# V1c.net
KiCad netlist of a schematic drawn in EAGLE
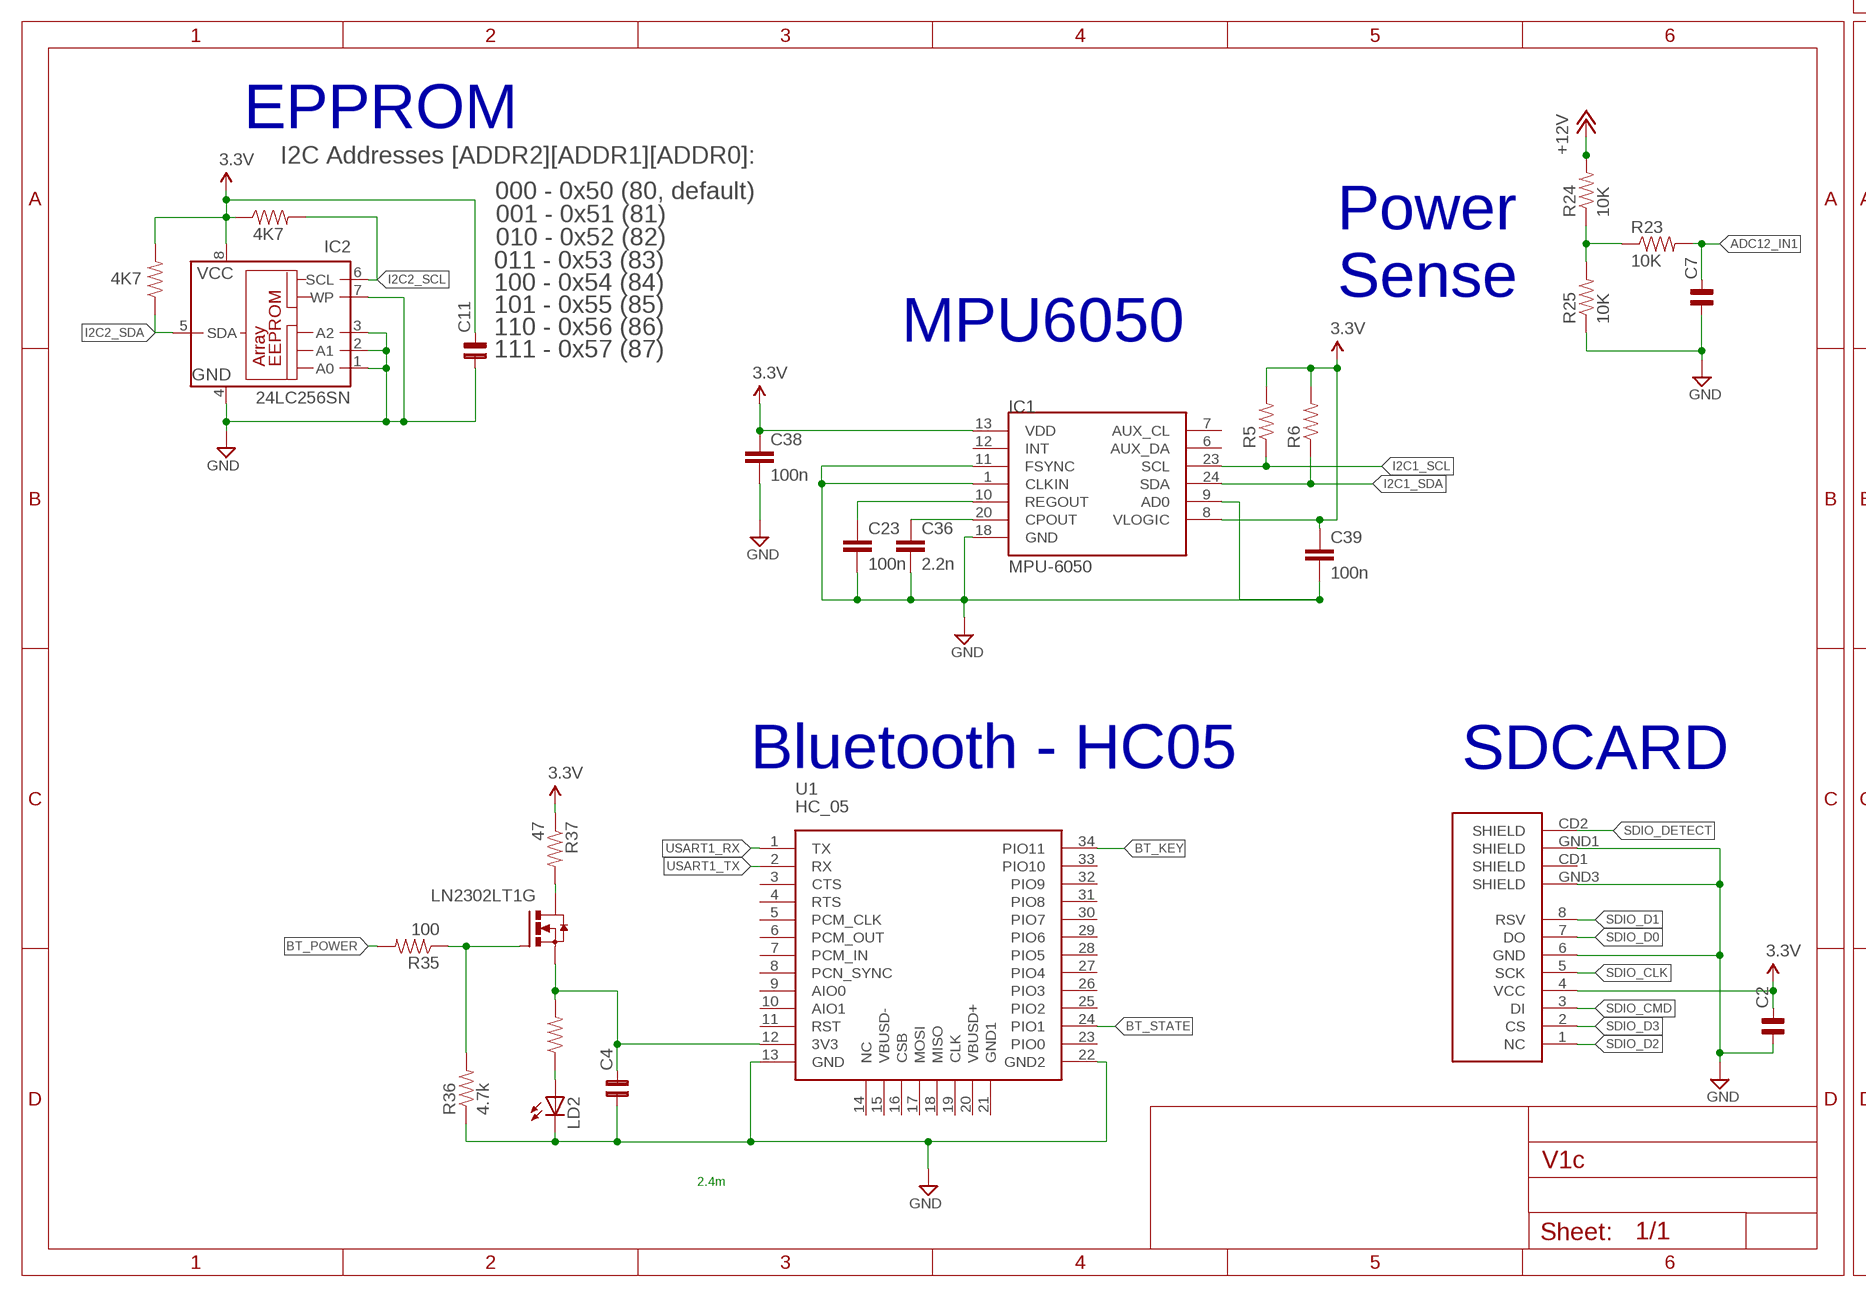
[diagram p0: schematic, sheet 1, part 1 of 2]
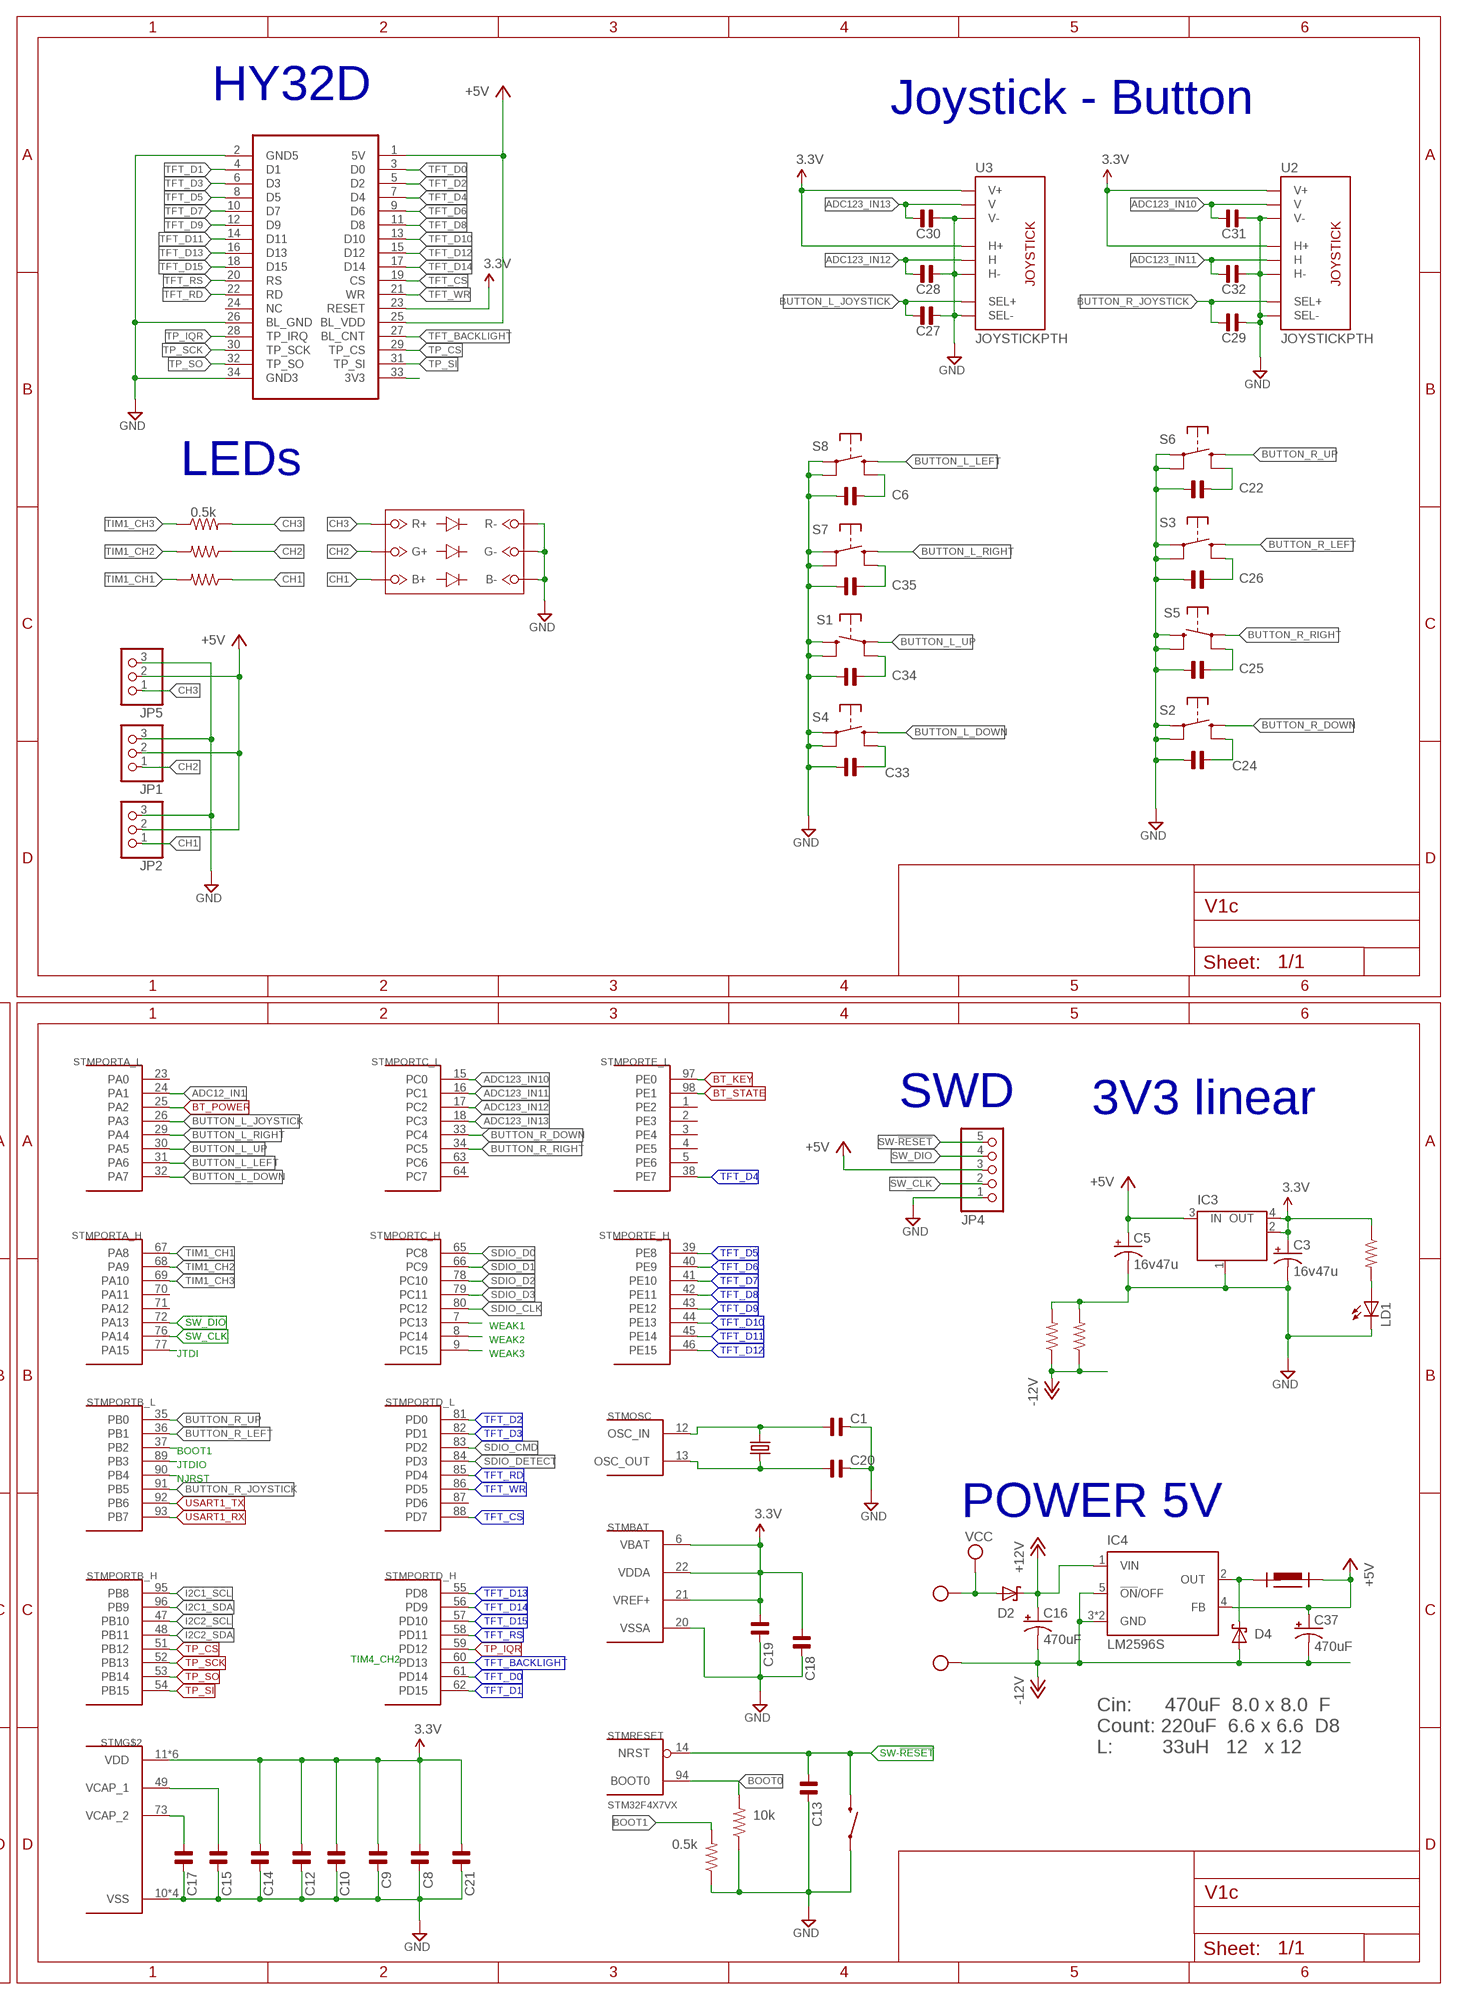
[diagram p1: schematic, sheet 1, part 2 of 2]

(export (version "E")
  (design (tool "Eeschema 10.0.6"))
  (components
    (comp (ref "C1")
      (value "C-NP-SMD-0603")
      (footprint "eagle-import:C-0603")
      (libsource (lib "eagle-import") (part "C-NP-SMD-0603"))
    )
    (comp (ref "C2")
      (value "C-NP-SMD-0603")
      (footprint "eagle-import:C-0603")
      (libsource (lib "eagle-import") (part "C-NP-SMD-0603"))
    )
    (comp (ref "C3")
      (value "16v47u")
      (footprint "eagle-import:SMC_C")
      (libsource (lib "eagle-import") (part "CPOL-USSMCC"))
    )
    (comp (ref "C4")
      (value "C-NP-SMD-0603")
      (footprint "eagle-import:C-0603")
      (libsource (lib "eagle-import") (part "C-NP-SMD-0603"))
    )
    (comp (ref "C5")
      (value "16v47u")
      (footprint "eagle-import:SMC_C")
      (libsource (lib "eagle-import") (part "CPOL-USSMCC"))
    )
    (comp (ref "C6")
      (value "C-NP-SMD-0603")
      (footprint "eagle-import:C-0603")
      (libsource (lib "eagle-import") (part "C-NP-SMD-0603"))
    )
    (comp (ref "C7")
      (value "C-NP-SMD-0603")
      (footprint "eagle-import:C-0603")
      (libsource (lib "eagle-import") (part "C-NP-SMD-0603"))
    )
    (comp (ref "C8")
      (value "C-NP-SMD-0603")
      (footprint "eagle-import:C-0603")
      (libsource (lib "eagle-import") (part "C-NP-SMD-0603"))
    )
    (comp (ref "C9")
      (value "C-NP-SMD-0603")
      (footprint "eagle-import:C-0603")
      (libsource (lib "eagle-import") (part "C-NP-SMD-0603"))
    )
    (comp (ref "C10")
      (value "C-NP-SMD-0603")
      (footprint "eagle-import:C-0603")
      (libsource (lib "eagle-import") (part "C-NP-SMD-0603"))
    )
    (comp (ref "C11")
      (value "C-NP-SMD-0603")
      (footprint "eagle-import:C-0603")
      (libsource (lib "eagle-import") (part "C-NP-SMD-0603"))
    )
    (comp (ref "C12")
      (value "C-NP-SMD-0603")
      (footprint "eagle-import:C-0603")
      (libsource (lib "eagle-import") (part "C-NP-SMD-0603"))
    )
    (comp (ref "C13")
      (value "C-NP-SMD-0603")
      (footprint "eagle-import:C-0603")
      (libsource (lib "eagle-import") (part "C-NP-SMD-0603"))
    )
    (comp (ref "C14")
      (value "C-NP-SMD-0603")
      (footprint "eagle-import:C-0603")
      (libsource (lib "eagle-import") (part "C-NP-SMD-0603"))
    )
    (comp (ref "C15")
      (value "C-NP-SMD-0603")
      (footprint "eagle-import:C-0603")
      (libsource (lib "eagle-import") (part "C-NP-SMD-0603"))
    )
    (comp (ref "C16")
      (value "470uF")
      (footprint "eagle-import:175TMP-0808")
      (libsource (lib "eagle-import") (part "CPOL-US175TMP-0808"))
    )
    (comp (ref "C17")
      (value "C-NP-SMD-0603")
      (footprint "eagle-import:C-0603")
      (libsource (lib "eagle-import") (part "C-NP-SMD-0603"))
    )
    (comp (ref "C18")
      (value "C-NP-SMD-0603")
      (footprint "eagle-import:C-0603")
      (libsource (lib "eagle-import") (part "C-NP-SMD-0603"))
    )
    (comp (ref "C19")
      (value "C-NP-SMD-0603")
      (footprint "eagle-import:C-0603")
      (libsource (lib "eagle-import") (part "C-NP-SMD-0603"))
    )
    (comp (ref "C20")
      (value "C-NP-SMD-0603")
      (footprint "eagle-import:C-0603")
      (libsource (lib "eagle-import") (part "C-NP-SMD-0603"))
    )
    (comp (ref "C21")
      (value "C-NP-SMD-0603")
      (footprint "eagle-import:C-0603")
      (libsource (lib "eagle-import") (part "C-NP-SMD-0603"))
    )
    (comp (ref "C22")
      (value "C-NP-SMD-0603")
      (footprint "eagle-import:C-0603")
      (libsource (lib "eagle-import") (part "C-NP-SMD-0603"))
    )
    (comp (ref "C23")
      (value "100n")
      (footprint "eagle-import:SPARKFUN_0603-CAP")
      (libsource (lib "eagle-import") (part "SPARKFUN_CAP0603-CAP"))
    )
    (comp (ref "C24")
      (value "C-NP-SMD-0603")
      (footprint "eagle-import:C-0603")
      (libsource (lib "eagle-import") (part "C-NP-SMD-0603"))
    )
    (comp (ref "C25")
      (value "C-NP-SMD-0603")
      (footprint "eagle-import:C-0603")
      (libsource (lib "eagle-import") (part "C-NP-SMD-0603"))
    )
    (comp (ref "C26")
      (value "C-NP-SMD-0603")
      (footprint "eagle-import:C-0603")
      (libsource (lib "eagle-import") (part "C-NP-SMD-0603"))
    )
    (comp (ref "C27")
      (value "C-NP-SMD-0603")
      (footprint "eagle-import:C-0603")
      (libsource (lib "eagle-import") (part "C-NP-SMD-0603"))
    )
    (comp (ref "C28")
      (value "C-NP-SMD-0603")
      (footprint "eagle-import:C-0603")
      (libsource (lib "eagle-import") (part "C-NP-SMD-0603"))
    )
    (comp (ref "C29")
      (value "C-NP-SMD-0603")
      (footprint "eagle-import:C-0603")
      (libsource (lib "eagle-import") (part "C-NP-SMD-0603"))
    )
    (comp (ref "C30")
      (value "C-NP-SMD-0603")
      (footprint "eagle-import:C-0603")
      (libsource (lib "eagle-import") (part "C-NP-SMD-0603"))
    )
    (comp (ref "C31")
      (value "C-NP-SMD-0603")
      (footprint "eagle-import:C-0603")
      (libsource (lib "eagle-import") (part "C-NP-SMD-0603"))
    )
    (comp (ref "C32")
      (value "C-NP-SMD-0603")
      (footprint "eagle-import:C-0603")
      (libsource (lib "eagle-import") (part "C-NP-SMD-0603"))
    )
    (comp (ref "C33")
      (value "C-NP-SMD-0603")
      (footprint "eagle-import:C-0603")
      (libsource (lib "eagle-import") (part "C-NP-SMD-0603"))
    )
    (comp (ref "C34")
      (value "C-NP-SMD-0603")
      (footprint "eagle-import:C-0603")
      (libsource (lib "eagle-import") (part "C-NP-SMD-0603"))
    )
    (comp (ref "C35")
      (value "C-NP-SMD-0603")
      (footprint "eagle-import:C-0603")
      (libsource (lib "eagle-import") (part "C-NP-SMD-0603"))
    )
    (comp (ref "C36")
      (value "2.2n")
      (footprint "eagle-import:SPARKFUN_0603-CAP")
      (libsource (lib "eagle-import") (part "SPARKFUN_CAP0603-CAP"))
    )
    (comp (ref "C37")
      (value "470uF")
      (footprint "eagle-import:E_7260-38W")
      (libsource (lib "eagle-import") (part "CPOL-USE/7260-38W"))
    )
    (comp (ref "C38")
      (value "100n")
      (footprint "eagle-import:SPARKFUN_0603-CAP")
      (libsource (lib "eagle-import") (part "SPARKFUN_CAP0603-CAP"))
    )
    (comp (ref "C39")
      (value "100n")
      (footprint "eagle-import:SPARKFUN_0603-CAP")
      (libsource (lib "eagle-import") (part "SPARKFUN_CAP0603-CAP"))
    )
    (comp (ref "D2")
      (value "MBRS330T3")
      (footprint "eagle-import:SMC")
      (libsource (lib "eagle-import") (part "MBRS30T33"))
    )
    (comp (ref "D4")
      (value "MBRS330T3")
      (footprint "eagle-import:SMC")
      (libsource (lib "eagle-import") (part "MBRS30T33"))
    )
    (comp (ref "IC1")
      (value "MPU-6050")
      (footprint "eagle-import:TESTING_QFN-24-4MM2")
      (libsource (lib "eagle-import") (part "TESTING_MPU-6050-1"))
    )
    (comp (ref "IC2")
      (value "24LC256SN")
      (footprint "eagle-import:SO-08")
      (fields (field (name "MF") "MICROCHIP") (field (name "MPN") "24LC256-I/SN"))
      (libsource (lib "eagle-import") (part "24SNLC256"))
    )
    (comp (ref "IC3")
      (value "LINEAR_MC33269ST-3.3T3")
      (footprint "eagle-import:LINEAR_SOT223")
      (libsource (lib "eagle-import") (part "LINEAR_MC33269ST-3.3T3"))
    )
    (comp (ref "IC4")
      (value "LM2596S")
      (footprint "eagle-import:TO263-5")
      (fields (field (name "MF") "NATIONAL SEMICONDUCTOR") (field (name "MPN") "LM2596S-ADJ/NOPB"))
      (libsource (lib "eagle-import") (part "LM2596S"))
    )
    (comp (ref "JP1")
      (value "PINHD-1X3_2.54-90°")
      (footprint "eagle-import:1X03_90")
      (libsource (lib "eagle-import") (part "PINHD-1X3_2.54-90°"))
    )
    (comp (ref "JP2")
      (value "PINHD-1X3_2.54-90°")
      (footprint "eagle-import:1X03_90")
      (libsource (lib "eagle-import") (part "PINHD-1X3_2.54-90°"))
    )
    (comp (ref "JP4")
      (value "PINHD-1X5_2.54-90°")
      (footprint "eagle-import:1X05_90")
      (libsource (lib "eagle-import") (part "PINHD-1X5_2.54-90°"))
    )
    (comp (ref "JP5")
      (value "PINHD-1X3_2.54-90°")
      (footprint "eagle-import:1X03_90")
      (libsource (lib "eagle-import") (part "PINHD-1X3_2.54-90°"))
    )
    (comp (ref "LD1")
      (value "LEDCHIPLED_0805")
      (footprint "eagle-import:CHIPLED_0805")
      (libsource (lib "eagle-import") (part "LEDCHIPLED_0805"))
    )
    (comp (ref "LD2")
      (value "LEDCHIPLED_0805")
      (footprint "eagle-import:CHIPLED_0805")
      (libsource (lib "eagle-import") (part "LEDCHIPLED_0805"))
    )
    (comp (ref "LN2302LT1G")
      (value "FDN327N")
      (footprint "eagle-import:SOT-23")
      (libsource (lib "eagle-import") (part "FDN327N"))
    )
    (comp (ref "R1")
      (value "10k")
      (footprint "eagle-import:SPARKFUN_0603-RES")
      (libsource (lib "eagle-import") (part "Robotech_RCL_SPARKFUN_RESISTOR0603-RES"))
    )
    (comp (ref "R2")
      (value "10k")
      (footprint "eagle-import:SPARKFUN_0603-RES")
      (libsource (lib "eagle-import") (part "Robotech_RCL_SPARKFUN_RESISTOR0603-RES"))
    )
    (comp (ref "R5")
      (value "SPARKFUN_RESISTOR0603-RES")
      (footprint "eagle-import:SPARKFUN_0603-RES")
      (libsource (lib "eagle-import") (part "Helios_RLC_SPARKFUN_RESISTOR0603-RES"))
    )
    (comp (ref "R6")
      (value "SPARKFUN_RESISTOR0603-RES")
      (footprint "eagle-import:SPARKFUN_0603-RES")
      (libsource (lib "eagle-import") (part "Helios_RLC_SPARKFUN_RESISTOR0603-RES"))
    )
    (comp (ref "R7")
      (value "10k")
      (footprint "eagle-import:SPARKFUN_0603-RES")
      (libsource (lib "eagle-import") (part "Robotech_RCL_SPARKFUN_RESISTOR0603-RES"))
    )
    (comp (ref "R8")
      (value "0.5k")
      (footprint "eagle-import:SPARKFUN_0603-RES")
      (libsource (lib "eagle-import") (part "Robotech_RCL_SPARKFUN_RESISTOR0603-RES"))
    )
    (comp (ref "R9")
      (value "10K")
      (footprint "eagle-import:SPARKFUN_0603-RES")
      (libsource (lib "eagle-import") (part "Robotech_RCL_SPARKFUN_RESISTOR0603-RES"))
    )
    (comp (ref "R10")
      (value "10K")
      (footprint "eagle-import:SPARKFUN_0603-RES")
      (libsource (lib "eagle-import") (part "Robotech_RCL_SPARKFUN_RESISTOR0603-RES"))
    )
    (comp (ref "R11")
      (value "10K")
      (footprint "eagle-import:SPARKFUN_0603-RES")
      (libsource (lib "eagle-import") (part "Robotech_RCL_SPARKFUN_RESISTOR0603-RES"))
    )
    (comp (ref "R12")
      (value "10K")
      (footprint "eagle-import:SPARKFUN_0603-RES")
      (fields (field (name "R32") "0.5k"))
      (libsource (lib "eagle-import") (part "Robotech_RCL_SPARKFUN_RESISTOR0603-RES"))
    )
    (comp (ref "R15")
      (value "4K7")
      (footprint "eagle-import:SPARKFUN_0603-RES")
      (libsource (lib "eagle-import") (part "Robotech_RCL_SPARKFUN_RESISTOR0603-RES"))
    )
    (comp (ref "R16")
      (value "4K7")
      (footprint "eagle-import:SPARKFUN_0603-RES")
      (libsource (lib "eagle-import") (part "Robotech_RCL_SPARKFUN_RESISTOR0603-RES"))
    )
    (comp (ref "R23")
      (value "10K")
      (footprint "eagle-import:SPARKFUN_0603-RES")
      (libsource (lib "eagle-import") (part "Robotech_RCL_SPARKFUN_RESISTOR0603-RES"))
    )
    (comp (ref "R24")
      (value "10K")
      (footprint "eagle-import:SPARKFUN_0603-RES")
      (libsource (lib "eagle-import") (part "Robotech_RCL_SPARKFUN_RESISTOR0603-RES"))
    )
    (comp (ref "R25")
      (value "10K")
      (footprint "eagle-import:SPARKFUN_0603-RES")
      (libsource (lib "eagle-import") (part "Robotech_RCL_SPARKFUN_RESISTOR0603-RES"))
    )
    (comp (ref "R35")
      (value "100")
      (footprint "eagle-import:SPARKFUN_0603-RES")
      (libsource (lib "eagle-import") (part "SPARKFUN_RESISTOR0603-RES"))
    )
    (comp (ref "R36")
      (value "4.7k")
      (footprint "eagle-import:SPARKFUN_0603-RES")
      (libsource (lib "eagle-import") (part "SPARKFUN_RESISTOR0603-RES"))
    )
    (comp (ref "R37")
      (value "47")
      (footprint "eagle-import:SPARKFUN_0603-RES")
      (libsource (lib "eagle-import") (part "SPARKFUN_RESISTOR0603-RES"))
    )
    (comp (ref "R39")
      (value "10K")
      (footprint "eagle-import:SPARKFUN_0603-RES")
      (libsource (lib "eagle-import") (part "Robotech_RCL_SPARKFUN_RESISTOR0603-RES"))
    )
    (comp (ref "S1")
      (value "RACON12/")
      (footprint "eagle-import:RACON12_")
      (libsource (lib "eagle-import") (part "RACON12/"))
    )
    (comp (ref "S2")
      (value "RACON12/")
      (footprint "eagle-import:RACON12_")
      (libsource (lib "eagle-import") (part "RACON12/"))
    )
    (comp (ref "S3")
      (value "RACON12/")
      (footprint "eagle-import:RACON12_")
      (libsource (lib "eagle-import") (part "RACON12/"))
    )
    (comp (ref "S4")
      (value "RACON12/")
      (footprint "eagle-import:RACON12_")
      (libsource (lib "eagle-import") (part "RACON12/"))
    )
    (comp (ref "S5")
      (value "RACON12/")
      (footprint "eagle-import:RACON12_")
      (libsource (lib "eagle-import") (part "RACON12/"))
    )
    (comp (ref "S6")
      (value "RACON12/")
      (footprint "eagle-import:RACON12_")
      (libsource (lib "eagle-import") (part "RACON12/"))
    )
    (comp (ref "S7")
      (value "RACON12/")
      (footprint "eagle-import:RACON12_")
      (libsource (lib "eagle-import") (part "RACON12/"))
    )
    (comp (ref "S8")
      (value "RACON12/")
      (footprint "eagle-import:RACON12_")
      (libsource (lib "eagle-import") (part "RACON12/"))
    )
    (comp (ref "S9")
      (value "RESET")
      (footprint "eagle-import:TACTILE-SWITCH-1101NE")
      (fields (field (name "PARTNO") "EVQ-P7J01P"))
      (libsource (lib "eagle-import") (part "SWITCH-MOMENTARY-2-SMD-1101NE"))
    )
    (comp (ref "SDCARD2")
      (value "microSD Socket")
      (footprint "eagle-import:MICRO-SD-SOCKET-PP")
      (libsource (lib "eagle-import") (part "USD-SOCKETNEW"))
    )
    (comp (ref "STM")
      (value "STM32F4X7VX")
      (footprint "eagle-import:TQFP100")
      (fields (field (name "PARTNO") "STM32F427VI"))
      (libsource (lib "eagle-import") (part "STM32F4X7VX"))
    )
    (comp (ref "U$3")
      (value "TFT3.2")
      (footprint "eagle-import:HY32D_2")
      (libsource (lib "eagle-import") (part "TFT3.2"))
    )
    (comp (ref "U$5")
      (value "BIG_INDUCTOR")
      (footprint "eagle-import:12X12")
      (libsource (lib "eagle-import") (part "BIG_INDUCTOR"))
    )
    (comp (ref "U$13")
      (value "RGB_LED")
      (footprint "eagle-import:SMD")
      (libsource (lib "eagle-import") (part "RGB_LED"))
    )
    (comp (ref "U1")
      (value "HC_05")
      (footprint "eagle-import:BLUETOOTH_SMD")
      (libsource (lib "eagle-import") (part "HC_05"))
    )
    (comp (ref "U2")
      (value "JOYSTICKPTH")
      (footprint "eagle-import:JOYSTICK")
      (libsource (lib "eagle-import") (part "JOYSTICKPTH"))
    )
    (comp (ref "U3")
      (value "JOYSTICKPTH")
      (footprint "eagle-import:JOYSTICK")
      (libsource (lib "eagle-import") (part "JOYSTICKPTH"))
    )
    (comp (ref "X1")
      (value "MKDSN1,5/2-5,08")
      (footprint "eagle-import:MKDSN1,5_2-5,08")
      (fields (field (name "MPN") "MKDSN 1,5/2-5.08"))
      (libsource (lib "eagle-import") (part "MKDSN1,5/2-5,08"))
    )
    (comp (ref "Y1")
      (value "CRYSTALHC49US")
      (footprint "eagle-import:HC49US")
      (libsource (lib "eagle-import") (part "CRYSTALHC49US"))
    )
  )
  (nets
    (net (code "1") (name "+5V") (class "Default")
      (node (ref "C37") (pin "+") (pinfunction "+_+") (pintype "passive"))
      (node (ref "C5") (pin "+") (pinfunction "+_+") (pintype "passive"))
      (node (ref "IC3") (pin "3") (pinfunction "IN_3") (pintype "input"))
      (node (ref "IC4") (pin "4") (pinfunction "FB_4") (pintype "input"))
      (node (ref "JP1") (pin "2") (pinfunction "2_2") (pintype "passive"))
      (node (ref "JP2") (pin "2") (pinfunction "2_2") (pintype "passive"))
      (node (ref "JP4") (pin "3") (pinfunction "3_3") (pintype "passive"))
      (node (ref "JP5") (pin "2") (pinfunction "2_2") (pintype "passive"))
      (node (ref "U$3") (pin "1") (pinfunction "5V_1") (pintype "bidirectional"))
      (node (ref "U$3") (pin "25") (pinfunction "BL_VDD_25") (pintype "bidirectional"))
      (node (ref "U$5") (pin "P$1") (pinfunction "P$1_P$1") (pintype "bidirectional"))
    )
    (net (code "2") (name "+12V") (class "Default")
      (node (ref "C16") (pin "+") (pinfunction "+_+") (pintype "passive"))
      (node (ref "D2") (pin "C") (pinfunction "C_C") (pintype "passive"))
      (node (ref "IC4") (pin "1") (pinfunction "VIN_1") (pintype "input"))
      (node (ref "R24") (pin "2") (pinfunction "2_2") (pintype "passive"))
    )
    (net (code "3") (name "-12V") (class "Default")
      (node (ref "C16") (pin "-") (pinfunction "-_-") (pintype "passive"))
      (node (ref "C37") (pin "-") (pinfunction "-_-") (pintype "passive"))
      (node (ref "D4") (pin "A") (pinfunction "A_A") (pintype "passive"))
      (node (ref "IC4") (pin "3") (pinfunction "GND_3") (pintype "power_in"))
      (node (ref "IC4") (pin "5") (pinfunction "~{ON}/OFF_5") (pintype "input"))
      (node (ref "IC4") (pin "6") (pinfunction "GND_6") (pintype "power_in"))
      (node (ref "R1") (pin "1") (pinfunction "1_1") (pintype "passive"))
      (node (ref "R2") (pin "1") (pinfunction "1_1") (pintype "passive"))
      (node (ref "X1") (pin "1") (pinfunction "KL_1") (pintype "passive"))
    )
    (net (code "4") (name "/JTDI") (class "Default")
      (node (ref "STM") (pin "77") (pinfunction "PA15_77") (pintype "bidirectional"))
    )
    (net (code "5") (name "/JTDIO") (class "Default")
      (node (ref "STM") (pin "89") (pinfunction "PB3_89") (pintype "bidirectional"))
    )
    (net (code "6") (name "/NJRST") (class "Default")
      (node (ref "STM") (pin "90") (pinfunction "PB4_90") (pintype "bidirectional"))
    )
    (net (code "7") (name "/SW-~{RESET}") (class "Default")
      (node (ref "C13") (pin "1") (pinfunction "1_1") (pintype "passive"))
      (node (ref "JP4") (pin "5") (pinfunction "5_5") (pintype "passive"))
      (node (ref "S9") (pin "P$2") (pinfunction "2_P$2") (pintype "passive"))
      (node (ref "STM") (pin "14") (pinfunction "NRST_14") (pintype "input"))
    )
    (net (code "8") (name "/WEAK1") (class "Default")
      (node (ref "STM") (pin "7") (pinfunction "PC13_7") (pintype "bidirectional"))
    )
    (net (code "9") (name "/WEAK2") (class "Default")
      (node (ref "STM") (pin "8") (pinfunction "PC14_8") (pintype "bidirectional"))
    )
    (net (code "10") (name "/WEAK3") (class "Default")
      (node (ref "STM") (pin "9") (pinfunction "PC15_9") (pintype "bidirectional"))
    )
    (net (code "11") (name "3.3V") (class "Default")
      (node (ref "C10") (pin "1") (pinfunction "1_1") (pintype "passive"))
      (node (ref "C11") (pin "2") (pinfunction "2_2") (pintype "passive"))
      (node (ref "C12") (pin "1") (pinfunction "1_1") (pintype "passive"))
      (node (ref "C14") (pin "1") (pinfunction "1_1") (pintype "passive"))
      (node (ref "C18") (pin "1") (pinfunction "1_1") (pintype "passive"))
      (node (ref "C19") (pin "1") (pinfunction "1_1") (pintype "passive"))
      (node (ref "C2") (pin "2") (pinfunction "2_2") (pintype "passive"))
      (node (ref "C21") (pin "1") (pinfunction "1_1") (pintype "passive"))
      (node (ref "C3") (pin "+") (pinfunction "+_+") (pintype "passive"))
      (node (ref "C38") (pin "1") (pinfunction "1_1") (pintype "passive"))
      (node (ref "C39") (pin "1") (pinfunction "1_1") (pintype "passive"))
      (node (ref "C8") (pin "1") (pinfunction "1_1") (pintype "passive"))
      (node (ref "C9") (pin "1") (pinfunction "1_1") (pintype "passive"))
      (node (ref "IC1") (pin "13") (pinfunction "VDD_13") (pintype "bidirectional"))
      (node (ref "IC1") (pin "8") (pinfunction "VLOGIC_8") (pintype "bidirectional"))
      (node (ref "IC2") (pin "8") (pinfunction "VCC_8") (pintype "power_in"))
      (node (ref "IC3") (pin "2") (pinfunction "OUT_2") (pintype "passive"))
      (node (ref "IC3") (pin "4") (pinfunction "OUT_4") (pintype "passive"))
      (node (ref "R15") (pin "1") (pinfunction "1_1") (pintype "passive"))
      (node (ref "R16") (pin "2") (pinfunction "2_2") (pintype "passive"))
      (node (ref "R37") (pin "1") (pinfunction "1_1") (pintype "passive"))
      (node (ref "R5") (pin "2") (pinfunction "2_2") (pintype "passive"))
      (node (ref "R6") (pin "2") (pinfunction "2_2") (pintype "passive"))
      (node (ref "R9") (pin "1") (pinfunction "1_1") (pintype "passive"))
      (node (ref "SDCARD2") (pin "4") (pinfunction "VCC_4") (pintype "bidirectional"))
      (node (ref "STM") (pin "100") (pinfunction "VDD_100") (pintype "power_in"))
      (node (ref "STM") (pin "11") (pinfunction "VDD_11") (pintype "power_in"))
      (node (ref "STM") (pin "19") (pinfunction "VDD_19") (pintype "power_in"))
      (node (ref "STM") (pin "21") (pinfunction "VREF+_21") (pintype "input"))
      (node (ref "STM") (pin "22") (pinfunction "VDDA_22") (pintype "power_in"))
      (node (ref "STM") (pin "28") (pinfunction "VDD_28") (pintype "power_in"))
      (node (ref "STM") (pin "50") (pinfunction "VDD_50") (pintype "power_in"))
      (node (ref "STM") (pin "6") (pinfunction "VBAT_6") (pintype "power_in"))
      (node (ref "STM") (pin "75") (pinfunction "VDD_75") (pintype "power_in"))
      (node (ref "U$3") (pin "23") (pinfunction "RESET_23") (pintype "bidirectional"))
      (node (ref "U2") (pin "H1") (pinfunction "H+_H1") (pintype "bidirectional"))
      (node (ref "U2") (pin "V1") (pinfunction "V+_V1") (pintype "bidirectional"))
      (node (ref "U3") (pin "H1") (pinfunction "H+_H1") (pintype "bidirectional"))
      (node (ref "U3") (pin "V1") (pinfunction "V+_V1") (pintype "bidirectional"))
    )
    (net (code "12") (name "ADC12_IN1") (class "Default")
      (node (ref "C7") (pin "2") (pinfunction "2_2") (pintype "passive"))
      (node (ref "R23") (pin "2") (pinfunction "2_2") (pintype "passive"))
      (node (ref "STM") (pin "24") (pinfunction "PA1_24") (pintype "bidirectional"))
    )
    (net (code "13") (name "ADC123_IN10") (class "Default")
      (node (ref "C31") (pin "1") (pinfunction "1_1") (pintype "passive"))
      (node (ref "STM") (pin "15") (pinfunction "PC0_15") (pintype "bidirectional"))
      (node (ref "U2") (pin "V2") (pinfunction "V_V2") (pintype "bidirectional"))
    )
    (net (code "14") (name "ADC123_IN11") (class "Default")
      (node (ref "C32") (pin "1") (pinfunction "1_1") (pintype "passive"))
      (node (ref "STM") (pin "16") (pinfunction "PC1_16") (pintype "bidirectional"))
      (node (ref "U2") (pin "H2") (pinfunction "H_H2") (pintype "bidirectional"))
    )
    (net (code "15") (name "ADC123_IN12") (class "Default")
      (node (ref "C28") (pin "1") (pinfunction "1_1") (pintype "passive"))
      (node (ref "STM") (pin "17") (pinfunction "PC2_17") (pintype "bidirectional"))
      (node (ref "U3") (pin "H2") (pinfunction "H_H2") (pintype "bidirectional"))
    )
    (net (code "16") (name "ADC123_IN13") (class "Default")
      (node (ref "C30") (pin "1") (pinfunction "1_1") (pintype "passive"))
      (node (ref "STM") (pin "18") (pinfunction "PC3_18") (pintype "bidirectional"))
      (node (ref "U3") (pin "V2") (pinfunction "V_V2") (pintype "bidirectional"))
    )
    (net (code "17") (name "BOOT0") (class "Default")
      (node (ref "R7") (pin "2") (pinfunction "2_2") (pintype "passive"))
      (node (ref "STM") (pin "94") (pinfunction "BOOT0_94") (pintype "input"))
    )
    (net (code "18") (name "BOOT1") (class "Default")
      (node (ref "R8") (pin "2") (pinfunction "2_2") (pintype "passive"))
      (node (ref "STM") (pin "37") (pinfunction "PB2_37") (pintype "bidirectional"))
    )
    (net (code "19") (name "BT_KEY") (class "Default")
      (node (ref "STM") (pin "97") (pinfunction "PE0_97") (pintype "bidirectional"))
      (node (ref "U1") (pin "34") (pinfunction "PIO11_34") (pintype "bidirectional"))
    )
    (net (code "20") (name "BT_POWER") (class "Default")
      (node (ref "R35") (pin "2") (pinfunction "2_2") (pintype "passive"))
      (node (ref "STM") (pin "25") (pinfunction "PA2_25") (pintype "bidirectional"))
    )
    (net (code "21") (name "BT_STATE") (class "Default")
      (node (ref "STM") (pin "98") (pinfunction "PE1_98") (pintype "bidirectional"))
      (node (ref "U1") (pin "24") (pinfunction "PIO1_24") (pintype "bidirectional"))
    )
    (net (code "22") (name "BUTTON_L_DOWN") (class "Default")
      (node (ref "S4") (pin "1") (pinfunction "S_1") (pintype "passive"))
      (node (ref "STM") (pin "32") (pinfunction "PA7_32") (pintype "bidirectional"))
    )
    (net (code "23") (name "BUTTON_L_JOYSTICK") (class "Default")
      (node (ref "C27") (pin "1") (pinfunction "1_1") (pintype "passive"))
      (node (ref "STM") (pin "26") (pinfunction "PA3_26") (pintype "bidirectional"))
      (node (ref "U3") (pin "B1A") (pinfunction "SEL+_B1A") (pintype "bidirectional"))
    )
    (net (code "24") (name "BUTTON_L_LEFT") (class "Default")
      (node (ref "S8") (pin "1") (pinfunction "S_1") (pintype "passive"))
      (node (ref "STM") (pin "31") (pinfunction "PA6_31") (pintype "bidirectional"))
    )
    (net (code "25") (name "BUTTON_L_RIGHT") (class "Default")
      (node (ref "S7") (pin "1") (pinfunction "S_1") (pintype "passive"))
      (node (ref "STM") (pin "29") (pinfunction "PA4_29") (pintype "bidirectional"))
    )
    (net (code "26") (name "BUTTON_L_UP") (class "Default")
      (node (ref "S1") (pin "3") (pinfunction "P_3") (pintype "passive"))
      (node (ref "STM") (pin "30") (pinfunction "PA5_30") (pintype "bidirectional"))
    )
    (net (code "27") (name "BUTTON_R_DOWN") (class "Default")
      (node (ref "S2") (pin "1") (pinfunction "S_1") (pintype "passive"))
      (node (ref "STM") (pin "33") (pinfunction "PC4_33") (pintype "bidirectional"))
    )
    (net (code "28") (name "BUTTON_R_JOYSTICK") (class "Default")
      (node (ref "C29") (pin "1") (pinfunction "1_1") (pintype "passive"))
      (node (ref "STM") (pin "91") (pinfunction "PB5_91") (pintype "bidirectional"))
      (node (ref "U2") (pin "B1A") (pinfunction "SEL+_B1A") (pintype "bidirectional"))
    )
    (net (code "29") (name "BUTTON_R_LEFT") (class "Default")
      (node (ref "S3") (pin "1") (pinfunction "S_1") (pintype "passive"))
      (node (ref "STM") (pin "36") (pinfunction "PB1_36") (pintype "bidirectional"))
    )
    (net (code "30") (name "BUTTON_R_RIGHT") (class "Default")
      (node (ref "S5") (pin "3") (pinfunction "P_3") (pintype "passive"))
      (node (ref "STM") (pin "34") (pinfunction "PC5_34") (pintype "bidirectional"))
    )
    (net (code "31") (name "BUTTON_R_UP") (class "Default")
      (node (ref "S6") (pin "1") (pinfunction "S_1") (pintype "passive"))
      (node (ref "STM") (pin "35") (pinfunction "PB0_35") (pintype "bidirectional"))
    )
    (net (code "32") (name "CH1") (class "Default")
      (node (ref "JP2") (pin "1") (pinfunction "1_1") (pintype "passive"))
      (node (ref "R11") (pin "1") (pinfunction "1_1") (pintype "passive"))
      (node (ref "U$13") (pin "B+") (pinfunction "B+_B+") (pintype "bidirectional"))
    )
    (net (code "33") (name "CH2") (class "Default")
      (node (ref "JP1") (pin "1") (pinfunction "1_1") (pintype "passive"))
      (node (ref "R39") (pin "1") (pinfunction "1_1") (pintype "passive"))
      (node (ref "U$13") (pin "G+") (pinfunction "G+_G+") (pintype "bidirectional"))
    )
    (net (code "34") (name "CH3") (class "Default")
      (node (ref "JP5") (pin "1") (pinfunction "1_1") (pintype "passive"))
      (node (ref "R12") (pin "2") (pinfunction "2_2") (pintype "passive"))
      (node (ref "U$13") (pin "R+") (pinfunction "R+_R+") (pintype "bidirectional"))
    )
    (net (code "35") (name "GND") (class "Default")
      (node (ref "C1") (pin "2") (pinfunction "2_2") (pintype "passive"))
      (node (ref "C10") (pin "2") (pinfunction "2_2") (pintype "passive"))
      (node (ref "C11") (pin "1") (pinfunction "1_1") (pintype "passive"))
      (node (ref "C12") (pin "2") (pinfunction "2_2") (pintype "passive"))
      (node (ref "C13") (pin "2") (pinfunction "2_2") (pintype "passive"))
      (node (ref "C14") (pin "2") (pinfunction "2_2") (pintype "passive"))
      (node (ref "C15") (pin "2") (pinfunction "2_2") (pintype "passive"))
      (node (ref "C17") (pin "2") (pinfunction "2_2") (pintype "passive"))
      (node (ref "C18") (pin "2") (pinfunction "2_2") (pintype "passive"))
      (node (ref "C19") (pin "2") (pinfunction "2_2") (pintype "passive"))
      (node (ref "C2") (pin "1") (pinfunction "1_1") (pintype "passive"))
      (node (ref "C20") (pin "2") (pinfunction "2_2") (pintype "passive"))
      (node (ref "C21") (pin "2") (pinfunction "2_2") (pintype "passive"))
      (node (ref "C22") (pin "1") (pinfunction "1_1") (pintype "passive"))
      (node (ref "C23") (pin "2") (pinfunction "2_2") (pintype "passive"))
      (node (ref "C24") (pin "2") (pinfunction "2_2") (pintype "passive"))
      (node (ref "C25") (pin "2") (pinfunction "2_2") (pintype "passive"))
      (node (ref "C26") (pin "2") (pinfunction "2_2") (pintype "passive"))
      (node (ref "C27") (pin "2") (pinfunction "2_2") (pintype "passive"))
      (node (ref "C28") (pin "2") (pinfunction "2_2") (pintype "passive"))
      (node (ref "C29") (pin "2") (pinfunction "2_2") (pintype "passive"))
      (node (ref "C3") (pin "-") (pinfunction "-_-") (pintype "passive"))
      (node (ref "C30") (pin "2") (pinfunction "2_2") (pintype "passive"))
      (node (ref "C31") (pin "2") (pinfunction "2_2") (pintype "passive"))
      (node (ref "C32") (pin "2") (pinfunction "2_2") (pintype "passive"))
      (node (ref "C33") (pin "2") (pinfunction "2_2") (pintype "passive"))
      (node (ref "C34") (pin "2") (pinfunction "2_2") (pintype "passive"))
      (node (ref "C35") (pin "2") (pinfunction "2_2") (pintype "passive"))
      (node (ref "C36") (pin "2") (pinfunction "2_2") (pintype "passive"))
      (node (ref "C38") (pin "2") (pinfunction "2_2") (pintype "passive"))
      (node (ref "C39") (pin "2") (pinfunction "2_2") (pintype "passive"))
      (node (ref "C4") (pin "1") (pinfunction "1_1") (pintype "passive"))
      (node (ref "C5") (pin "-") (pinfunction "-_-") (pintype "passive"))
      (node (ref "C6") (pin "1") (pinfunction "1_1") (pintype "passive"))
      (node (ref "C7") (pin "1") (pinfunction "1_1") (pintype "passive"))
      (node (ref "C8") (pin "2") (pinfunction "2_2") (pintype "passive"))
      (node (ref "C9") (pin "2") (pinfunction "2_2") (pintype "passive"))
      (node (ref "IC1") (pin "1") (pinfunction "CLKIN_1") (pintype "bidirectional"))
      (node (ref "IC1") (pin "11") (pinfunction "FSYNC_11") (pintype "bidirectional"))
      (node (ref "IC1") (pin "18") (pinfunction "GND_18") (pintype "bidirectional"))
      (node (ref "IC1") (pin "9") (pinfunction "AD0_9") (pintype "bidirectional"))
      (node (ref "IC2") (pin "1") (pinfunction "A0_1") (pintype "input"))
      (node (ref "IC2") (pin "2") (pinfunction "A1_2") (pintype "input"))
      (node (ref "IC2") (pin "3") (pinfunction "A2_3") (pintype "input"))
      (node (ref "IC2") (pin "4") (pinfunction "GND_4") (pintype "power_in"))
      (node (ref "IC2") (pin "7") (pinfunction "WP_7") (pintype "input"))
      (node (ref "IC3") (pin "1") (pinfunction "GND/ADJ_1") (pintype "input"))
      (node (ref "JP1") (pin "3") (pinfunction "3_3") (pintype "passive"))
      (node (ref "JP2") (pin "3") (pinfunction "3_3") (pintype "passive"))
      (node (ref "JP4") (pin "1") (pinfunction "1_1") (pintype "passive"))
      (node (ref "JP5") (pin "3") (pinfunction "3_3") (pintype "passive"))
      (node (ref "LD1") (pin "C") (pinfunction "C_C") (pintype "passive"))
      (node (ref "LD2") (pin "C") (pinfunction "C_C") (pintype "passive"))
      (node (ref "R1") (pin "2") (pinfunction "2_2") (pintype "passive"))
      (node (ref "R2") (pin "2") (pinfunction "2_2") (pintype "passive"))
      (node (ref "R25") (pin "1") (pinfunction "1_1") (pintype "passive"))
      (node (ref "R36") (pin "1") (pinfunction "1_1") (pintype "passive"))
      (node (ref "R7") (pin "1") (pinfunction "1_1") (pintype "passive"))
      (node (ref "R8") (pin "1") (pinfunction "1_1") (pintype "passive"))
      (node (ref "S1") (pin "1") (pinfunction "S_1") (pintype "passive"))
      (node (ref "S1") (pin "2") (pinfunction "S_2") (pintype "passive"))
      (node (ref "S2") (pin "3") (pinfunction "P_3") (pintype "passive"))
      (node (ref "S2") (pin "4") (pinfunction "P_4") (pintype "passive"))
      (node (ref "S3") (pin "3") (pinfunction "P_3") (pintype "passive"))
      (node (ref "S3") (pin "4") (pinfunction "P_4") (pintype "passive"))
      (node (ref "S4") (pin "3") (pinfunction "P_3") (pintype "passive"))
      (node (ref "S4") (pin "4") (pinfunction "P_4") (pintype "passive"))
      (node (ref "S5") (pin "1") (pinfunction "S_1") (pintype "passive"))
      (node (ref "S5") (pin "2") (pinfunction "S_2") (pintype "passive"))
      (node (ref "S6") (pin "3") (pinfunction "P_3") (pintype "passive"))
      (node (ref "S6") (pin "4") (pinfunction "P_4") (pintype "passive"))
      (node (ref "S7") (pin "3") (pinfunction "P_3") (pintype "passive"))
      (node (ref "S7") (pin "4") (pinfunction "P_4") (pintype "passive"))
      (node (ref "S8") (pin "3") (pinfunction "P_3") (pintype "passive"))
      (node (ref "S8") (pin "4") (pinfunction "P_4") (pintype "passive"))
      (node (ref "S9") (pin "P$1") (pinfunction "1_P$1") (pintype "passive"))
      (node (ref "SDCARD2") (pin "6") (pinfunction "GND_6") (pintype "bidirectional"))
      (node (ref "SDCARD2") (pin "GND1") (pinfunction "SHIELD_GND1") (pintype "bidirectional"))
      (node (ref "SDCARD2") (pin "GND3") (pinfunction "SHIELD_GND3") (pintype "bidirectional"))
      (node (ref "STM") (pin "10") (pinfunction "VSS_10") (pintype "power_in"))
      (node (ref "STM") (pin "20") (pinfunction "VSSA_20") (pintype "power_in"))
      (node (ref "STM") (pin "27") (pinfunction "VSS_27") (pintype "power_in"))
      (node (ref "STM") (pin "74") (pinfunction "VSS_74") (pintype "power_in"))
      (node (ref "STM") (pin "99") (pinfunction "VSS_99") (pintype "power_in"))
      (node (ref "U$13") (pin "B-") (pinfunction "B-_B-") (pintype "bidirectional"))
      (node (ref "U$13") (pin "G-") (pinfunction "G-_G-") (pintype "bidirectional"))
      (node (ref "U$13") (pin "R-") (pinfunction "R-_R-") (pintype "bidirectional"))
      (node (ref "U$3") (pin "2") (pinfunction "GND5_2") (pintype "bidirectional"))
      (node (ref "U$3") (pin "26") (pinfunction "BL_GND_26") (pintype "bidirectional"))
      (node (ref "U$3") (pin "34") (pinfunction "GND3_34") (pintype "bidirectional"))
      (node (ref "U1") (pin "13") (pinfunction "GND_13") (pintype "bidirectional"))
      (node (ref "U1") (pin "22") (pinfunction "GND2_22") (pintype "bidirectional"))
      (node (ref "U2") (pin "B2A") (pinfunction "SEL-_B2A") (pintype "bidirectional"))
      (node (ref "U2") (pin "H3") (pinfunction "H-_H3") (pintype "bidirectional"))
      (node (ref "U2") (pin "V3") (pinfunction "V-_V3") (pintype "bidirectional"))
      (node (ref "U3") (pin "B2A") (pinfunction "SEL-_B2A") (pintype "bidirectional"))
      (node (ref "U3") (pin "H3") (pinfunction "H-_H3") (pintype "bidirectional"))
      (node (ref "U3") (pin "V3") (pinfunction "V-_V3") (pintype "bidirectional"))
    )
    (net (code "36") (name "I2C1_SCL") (class "Default")
      (node (ref "IC1") (pin "23") (pinfunction "SCL_23") (pintype "bidirectional"))
      (node (ref "R5") (pin "1") (pinfunction "1_1") (pintype "passive"))
      (node (ref "STM") (pin "95") (pinfunction "PB8_95") (pintype "bidirectional"))
    )
    (net (code "37") (name "I2C1_SDA") (class "Default")
      (node (ref "IC1") (pin "24") (pinfunction "SDA_24") (pintype "bidirectional"))
      (node (ref "R6") (pin "1") (pinfunction "1_1") (pintype "passive"))
      (node (ref "STM") (pin "96") (pinfunction "PB9_96") (pintype "bidirectional"))
    )
    (net (code "38") (name "I2C2_SCL") (class "Default")
      (node (ref "IC2") (pin "6") (pinfunction "SCL_6") (pintype "input"))
      (node (ref "R15") (pin "2") (pinfunction "2_2") (pintype "passive"))
      (node (ref "STM") (pin "47") (pinfunction "PB10_47") (pintype "bidirectional"))
    )
    (net (code "39") (name "I2C2_SDA") (class "Default")
      (node (ref "IC2") (pin "5") (pinfunction "SDA_5") (pintype "bidirectional"))
      (node (ref "R16") (pin "1") (pinfunction "1_1") (pintype "passive"))
      (node (ref "STM") (pin "48") (pinfunction "PB11_48") (pintype "bidirectional"))
    )
    (net (code "40") (name "Net-(C6-Pad2)") (class "Default")
      (node (ref "C6") (pin "2") (pinfunction "2_2") (pintype "passive"))
      (node (ref "S8") (pin "2") (pinfunction "S_2") (pintype "passive"))
    )
    (net (code "41") (name "Net-(C22-Pad2)") (class "Default")
      (node (ref "C22") (pin "2") (pinfunction "2_2") (pintype "passive"))
      (node (ref "S6") (pin "2") (pinfunction "S_2") (pintype "passive"))
    )
    (net (code "42") (name "Net-(C24-Pad1)") (class "Default")
      (node (ref "C24") (pin "1") (pinfunction "1_1") (pintype "passive"))
      (node (ref "S2") (pin "2") (pinfunction "S_2") (pintype "passive"))
    )
    (net (code "43") (name "Net-(C25-Pad1)") (class "Default")
      (node (ref "C25") (pin "1") (pinfunction "1_1") (pintype "passive"))
      (node (ref "S5") (pin "4") (pinfunction "P_4") (pintype "passive"))
    )
    (net (code "44") (name "Net-(C26-Pad1)") (class "Default")
      (node (ref "C26") (pin "1") (pinfunction "1_1") (pintype "passive"))
      (node (ref "S3") (pin "2") (pinfunction "S_2") (pintype "passive"))
    )
    (net (code "45") (name "Net-(C33-Pad1)") (class "Default")
      (node (ref "C33") (pin "1") (pinfunction "1_1") (pintype "passive"))
      (node (ref "S4") (pin "2") (pinfunction "S_2") (pintype "passive"))
    )
    (net (code "46") (name "Net-(C34-Pad1)") (class "Default")
      (node (ref "C34") (pin "1") (pinfunction "1_1") (pintype "passive"))
      (node (ref "S1") (pin "4") (pinfunction "P_4") (pintype "passive"))
    )
    (net (code "47") (name "Net-(C35-Pad1)") (class "Default")
      (node (ref "C35") (pin "1") (pinfunction "1_1") (pintype "passive"))
      (node (ref "S7") (pin "2") (pinfunction "S_2") (pintype "passive"))
    )
    (net (code "48") (name "Net-(IC1-CPOUT)") (class "Default")
      (node (ref "C36") (pin "1") (pinfunction "1_1") (pintype "passive"))
      (node (ref "IC1") (pin "20") (pinfunction "CPOUT_20") (pintype "bidirectional"))
    )
    (net (code "49") (name "Net-(IC1-REGOUT)") (class "Default")
      (node (ref "C23") (pin "1") (pinfunction "1_1") (pintype "passive"))
      (node (ref "IC1") (pin "10") (pinfunction "REGOUT_10") (pintype "bidirectional"))
    )
    (net (code "50") (name "Net-(IC4-OUT)") (class "Default")
      (node (ref "D4") (pin "C") (pinfunction "C_C") (pintype "passive"))
      (node (ref "IC4") (pin "2") (pinfunction "OUT_2") (pintype "output"))
      (node (ref "U$5") (pin "P$2") (pinfunction "P$2_P$2") (pintype "bidirectional"))
    )
    (net (code "51") (name "Net-(LD1-PadA)") (class "Default")
      (node (ref "LD1") (pin "A") (pinfunction "A_A") (pintype "passive"))
      (node (ref "R9") (pin "2") (pinfunction "2_2") (pintype "passive"))
    )
    (net (code "52") (name "Net-(LD2-PadA)") (class "Default")
      (node (ref "LD2") (pin "A") (pinfunction "A_A") (pintype "passive"))
      (node (ref "R10") (pin "1") (pinfunction "1_1") (pintype "passive"))
    )
    (net (code "53") (name "Net-(LN2302LT1G-D)") (class "Default")
      (node (ref "LN2302LT1G") (pin "3") (pinfunction "D_3") (pintype "passive"))
      (node (ref "R37") (pin "2") (pinfunction "2_2") (pintype "passive"))
    )
    (net (code "54") (name "Net-(LN2302LT1G-G)") (class "Default")
      (node (ref "LN2302LT1G") (pin "1") (pinfunction "G_1") (pintype "passive"))
      (node (ref "R35") (pin "1") (pinfunction "1_1") (pintype "passive"))
      (node (ref "R36") (pin "2") (pinfunction "2_2") (pintype "passive"))
    )
    (net (code "55") (name "Net-(LN2302LT1G-S)") (class "Default")
      (node (ref "C4") (pin "2") (pinfunction "2_2") (pintype "passive"))
      (node (ref "LN2302LT1G") (pin "2") (pinfunction "S_2") (pintype "passive"))
      (node (ref "R10") (pin "2") (pinfunction "2_2") (pintype "passive"))
      (node (ref "U1") (pin "12") (pinfunction "3V3_12") (pintype "bidirectional"))
    )
    (net (code "56") (name "Net-(R23-Pad1)") (class "Default")
      (node (ref "R23") (pin "1") (pinfunction "1_1") (pintype "passive"))
      (node (ref "R24") (pin "1") (pinfunction "1_1") (pintype "passive"))
      (node (ref "R25") (pin "2") (pinfunction "2_2") (pintype "passive"))
    )
    (net (code "57") (name "Net-(STMB-VCAP_1)") (class "Default")
      (node (ref "C15") (pin "1") (pinfunction "1_1") (pintype "passive"))
      (node (ref "STM") (pin "49") (pinfunction "VCAP_1_49") (pintype "power_in"))
    )
    (net (code "58") (name "Net-(STMB-VCAP_2)") (class "Default")
      (node (ref "C17") (pin "1") (pinfunction "1_1") (pintype "passive"))
      (node (ref "STM") (pin "73") (pinfunction "VCAP_2_73") (pintype "power_in"))
    )
    (net (code "59") (name "Net-(STMC-OSC_IN)") (class "Default")
      (node (ref "C1") (pin "1") (pinfunction "1_1") (pintype "passive"))
      (node (ref "STM") (pin "12") (pinfunction "OSC_IN_12") (pintype "input"))
      (node (ref "Y1") (pin "2") (pinfunction "2_2") (pintype "passive"))
    )
    (net (code "60") (name "Net-(STMC-OSC_OUT)") (class "Default")
      (node (ref "C20") (pin "1") (pinfunction "1_1") (pintype "passive"))
      (node (ref "STM") (pin "13") (pinfunction "OSC_OUT_13") (pintype "output"))
      (node (ref "Y1") (pin "1") (pinfunction "1_1") (pintype "passive"))
    )
    (net (code "61") (name "SDIO_CLK") (class "Default")
      (node (ref "SDCARD2") (pin "5") (pinfunction "SCK_5") (pintype "bidirectional"))
      (node (ref "STM") (pin "80") (pinfunction "PC12_80") (pintype "bidirectional"))
    )
    (net (code "62") (name "SDIO_CMD") (class "Default")
      (node (ref "SDCARD2") (pin "3") (pinfunction "DI_3") (pintype "bidirectional"))
      (node (ref "STM") (pin "83") (pinfunction "PD2_83") (pintype "bidirectional"))
    )
    (net (code "63") (name "SDIO_D0") (class "Default")
      (node (ref "SDCARD2") (pin "7") (pinfunction "DO_7") (pintype "bidirectional"))
      (node (ref "STM") (pin "65") (pinfunction "PC8_65") (pintype "bidirectional"))
    )
    (net (code "64") (name "SDIO_D1") (class "Default")
      (node (ref "SDCARD2") (pin "8") (pinfunction "RSV_8") (pintype "bidirectional"))
      (node (ref "STM") (pin "66") (pinfunction "PC9_66") (pintype "bidirectional"))
    )
    (net (code "65") (name "SDIO_D2") (class "Default")
      (node (ref "SDCARD2") (pin "1") (pinfunction "NC_1") (pintype "bidirectional"))
      (node (ref "STM") (pin "78") (pinfunction "PC10_78") (pintype "bidirectional"))
    )
    (net (code "66") (name "SDIO_D3") (class "Default")
      (node (ref "SDCARD2") (pin "2") (pinfunction "CS_2") (pintype "bidirectional"))
      (node (ref "STM") (pin "79") (pinfunction "PC11_79") (pintype "bidirectional"))
    )
    (net (code "67") (name "SDIO_DETECT") (class "Default")
      (node (ref "SDCARD2") (pin "CD2") (pinfunction "SHIELD_CD2") (pintype "bidirectional"))
      (node (ref "STM") (pin "84") (pinfunction "PD3_84") (pintype "bidirectional"))
    )
    (net (code "68") (name "SW_CLK") (class "Default")
      (node (ref "JP4") (pin "2") (pinfunction "2_2") (pintype "passive"))
      (node (ref "STM") (pin "76") (pinfunction "PA14_76") (pintype "bidirectional"))
    )
    (net (code "69") (name "SW_DIO") (class "Default")
      (node (ref "JP4") (pin "4") (pinfunction "4_4") (pintype "passive"))
      (node (ref "STM") (pin "72") (pinfunction "PA13_72") (pintype "bidirectional"))
    )
    (net (code "70") (name "TFT_BACKLIGHT") (class "Default")
      (node (ref "STM") (pin "60") (pinfunction "PD13_60") (pintype "bidirectional"))
      (node (ref "U$3") (pin "27") (pinfunction "BL_CNT_27") (pintype "bidirectional"))
    )
    (net (code "71") (name "TFT_CS") (class "Default")
      (node (ref "STM") (pin "88") (pinfunction "PD7_88") (pintype "bidirectional"))
      (node (ref "U$3") (pin "19") (pinfunction "CS_19") (pintype "bidirectional"))
    )
    (net (code "72") (name "TFT_D0") (class "Default")
      (node (ref "STM") (pin "61") (pinfunction "PD14_61") (pintype "bidirectional"))
      (node (ref "U$3") (pin "3") (pinfunction "D0_3") (pintype "bidirectional"))
    )
    (net (code "73") (name "TFT_D1") (class "Default")
      (node (ref "STM") (pin "62") (pinfunction "PD15_62") (pintype "bidirectional"))
      (node (ref "U$3") (pin "4") (pinfunction "D1_4") (pintype "bidirectional"))
    )
    (net (code "74") (name "TFT_D2") (class "Default")
      (node (ref "STM") (pin "81") (pinfunction "PD0_81") (pintype "bidirectional"))
      (node (ref "U$3") (pin "5") (pinfunction "D2_5") (pintype "bidirectional"))
    )
    (net (code "75") (name "TFT_D3") (class "Default")
      (node (ref "STM") (pin "82") (pinfunction "PD1_82") (pintype "bidirectional"))
      (node (ref "U$3") (pin "6") (pinfunction "D3_6") (pintype "bidirectional"))
    )
    (net (code "76") (name "TFT_D4") (class "Default")
      (node (ref "STM") (pin "38") (pinfunction "PE7_38") (pintype "bidirectional"))
      (node (ref "U$3") (pin "7") (pinfunction "D4_7") (pintype "bidirectional"))
    )
    (net (code "77") (name "TFT_D5") (class "Default")
      (node (ref "STM") (pin "39") (pinfunction "PE8_39") (pintype "bidirectional"))
      (node (ref "U$3") (pin "8") (pinfunction "D5_8") (pintype "bidirectional"))
    )
    (net (code "78") (name "TFT_D6") (class "Default")
      (node (ref "STM") (pin "40") (pinfunction "PE9_40") (pintype "bidirectional"))
      (node (ref "U$3") (pin "9") (pinfunction "D6_9") (pintype "bidirectional"))
    )
    (net (code "79") (name "TFT_D7") (class "Default")
      (node (ref "STM") (pin "41") (pinfunction "PE10_41") (pintype "bidirectional"))
      (node (ref "U$3") (pin "10") (pinfunction "D7_10") (pintype "bidirectional"))
    )
    (net (code "80") (name "TFT_D8") (class "Default")
      (node (ref "STM") (pin "42") (pinfunction "PE11_42") (pintype "bidirectional"))
      (node (ref "U$3") (pin "11") (pinfunction "D8_11") (pintype "bidirectional"))
    )
    (net (code "81") (name "TFT_D9") (class "Default")
      (node (ref "STM") (pin "43") (pinfunction "PE12_43") (pintype "bidirectional"))
      (node (ref "U$3") (pin "12") (pinfunction "D9_12") (pintype "bidirectional"))
    )
    (net (code "82") (name "TFT_D10") (class "Default")
      (node (ref "STM") (pin "44") (pinfunction "PE13_44") (pintype "bidirectional"))
      (node (ref "U$3") (pin "13") (pinfunction "D10_13") (pintype "bidirectional"))
    )
    (net (code "83") (name "TFT_D11") (class "Default")
      (node (ref "STM") (pin "45") (pinfunction "PE14_45") (pintype "bidirectional"))
      (node (ref "U$3") (pin "14") (pinfunction "D11_14") (pintype "bidirectional"))
    )
    (net (code "84") (name "TFT_D12") (class "Default")
      (node (ref "STM") (pin "46") (pinfunction "PE15_46") (pintype "bidirectional"))
      (node (ref "U$3") (pin "15") (pinfunction "D12_15") (pintype "bidirectional"))
    )
    (net (code "85") (name "TFT_D13") (class "Default")
      (node (ref "STM") (pin "55") (pinfunction "PD8_55") (pintype "bidirectional"))
      (node (ref "U$3") (pin "16") (pinfunction "D13_16") (pintype "bidirectional"))
    )
    (net (code "86") (name "TFT_D14") (class "Default")
      (node (ref "STM") (pin "56") (pinfunction "PD9_56") (pintype "bidirectional"))
      (node (ref "U$3") (pin "17") (pinfunction "D14_17") (pintype "bidirectional"))
    )
    (net (code "87") (name "TFT_D15") (class "Default")
      (node (ref "STM") (pin "57") (pinfunction "PD10_57") (pintype "bidirectional"))
      (node (ref "U$3") (pin "18") (pinfunction "D15_18") (pintype "bidirectional"))
    )
    (net (code "88") (name "TFT_RD") (class "Default")
      (node (ref "STM") (pin "85") (pinfunction "PD4_85") (pintype "bidirectional"))
      (node (ref "U$3") (pin "22") (pinfunction "RD_22") (pintype "bidirectional"))
    )
    (net (code "89") (name "TFT_RS") (class "Default")
      (node (ref "STM") (pin "58") (pinfunction "PD11_58") (pintype "bidirectional"))
      (node (ref "U$3") (pin "20") (pinfunction "RS_20") (pintype "bidirectional"))
    )
    (net (code "90") (name "TFT_WR") (class "Default")
      (node (ref "STM") (pin "86") (pinfunction "PD5_86") (pintype "bidirectional"))
      (node (ref "U$3") (pin "21") (pinfunction "WR_21") (pintype "bidirectional"))
    )
    (net (code "91") (name "TIM1_CH1") (class "Default")
      (node (ref "R11") (pin "2") (pinfunction "2_2") (pintype "passive"))
      (node (ref "STM") (pin "67") (pinfunction "PA8_67") (pintype "bidirectional"))
    )
    (net (code "92") (name "TIM1_CH2") (class "Default")
      (node (ref "R39") (pin "2") (pinfunction "2_2") (pintype "passive"))
      (node (ref "STM") (pin "68") (pinfunction "PA9_68") (pintype "bidirectional"))
    )
    (net (code "93") (name "TIM1_CH3") (class "Default")
      (node (ref "R12") (pin "1") (pinfunction "1_1") (pintype "passive"))
      (node (ref "STM") (pin "69") (pinfunction "PA10_69") (pintype "bidirectional"))
    )
    (net (code "94") (name "TP_CS") (class "Default")
      (node (ref "STM") (pin "51") (pinfunction "PB12_51") (pintype "bidirectional"))
      (node (ref "U$3") (pin "29") (pinfunction "TP_CS_29") (pintype "bidirectional"))
    )
    (net (code "95") (name "TP_IQR") (class "Default")
      (node (ref "STM") (pin "59") (pinfunction "PD12_59") (pintype "bidirectional"))
      (node (ref "U$3") (pin "28") (pinfunction "TP_IRQ_28") (pintype "bidirectional"))
    )
    (net (code "96") (name "TP_SCK") (class "Default")
      (node (ref "STM") (pin "52") (pinfunction "PB13_52") (pintype "bidirectional"))
      (node (ref "U$3") (pin "30") (pinfunction "TP_SCK_30") (pintype "bidirectional"))
    )
    (net (code "97") (name "TP_SI") (class "Default")
      (node (ref "STM") (pin "54") (pinfunction "PB15_54") (pintype "bidirectional"))
      (node (ref "U$3") (pin "31") (pinfunction "TP_SI_31") (pintype "bidirectional"))
    )
    (net (code "98") (name "TP_SO") (class "Default")
      (node (ref "STM") (pin "53") (pinfunction "PB14_53") (pintype "bidirectional"))
      (node (ref "U$3") (pin "32") (pinfunction "TP_SO_32") (pintype "bidirectional"))
    )
    (net (code "99") (name "USART1_RX") (class "Default")
      (node (ref "STM") (pin "93") (pinfunction "PB7_93") (pintype "bidirectional"))
      (node (ref "U1") (pin "1") (pinfunction "TX_1") (pintype "bidirectional"))
    )
    (net (code "100") (name "USART1_TX") (class "Default")
      (node (ref "STM") (pin "92") (pinfunction "PB6_92") (pintype "bidirectional"))
      (node (ref "U1") (pin "2") (pinfunction "RX_2") (pintype "bidirectional"))
    )
    (net (code "101") (name "VCC") (class "Default")
      (node (ref "D2") (pin "A") (pinfunction "A_A") (pintype "passive"))
      (node (ref "X1") (pin "2") (pinfunction "KL_2") (pintype "passive"))
    )
    (net (code "102") (name "unconnected-(IC1-AUX_CL-Pad7)") (class "Default")
      (node (ref "IC1") (pin "7") (pinfunction "AUX_CL_7") (pintype "bidirectional"))
    )
    (net (code "103") (name "unconnected-(IC1-AUX_DA-Pad6)") (class "Default")
      (node (ref "IC1") (pin "6") (pinfunction "AUX_DA_6") (pintype "bidirectional"))
    )
    (net (code "104") (name "unconnected-(IC1-INT-Pad12)") (class "Default")
      (node (ref "IC1") (pin "12") (pinfunction "INT_12") (pintype "bidirectional"))
    )
    (net (code "105") (name "unconnected-(SDCARD2-SHIELD-PadCD1)") (class "Default")
      (node (ref "SDCARD2") (pin "CD1") (pinfunction "SHIELD_CD1") (pintype "bidirectional"))
    )
    (net (code "106") (name "unconnected-(STMD-PA11-Pad70)") (class "Default")
      (node (ref "STM") (pin "70") (pinfunction "PA11_70") (pintype "bidirectional"))
    )
    (net (code "107") (name "unconnected-(STMD-PA12-Pad71)") (class "Default")
      (node (ref "STM") (pin "71") (pinfunction "PA12_71") (pintype "bidirectional"))
    )
    (net (code "108") (name "unconnected-(STME-PA0-Pad23)") (class "Default")
      (node (ref "STM") (pin "23") (pinfunction "PA0_23") (pintype "bidirectional"))
    )
    (net (code "109") (name "unconnected-(STMI-PC6-Pad63)") (class "Default")
      (node (ref "STM") (pin "63") (pinfunction "PC6_63") (pintype "bidirectional"))
    )
    (net (code "110") (name "unconnected-(STMI-PC7-Pad64)") (class "Default")
      (node (ref "STM") (pin "64") (pinfunction "PC7_64") (pintype "bidirectional"))
    )
    (net (code "111") (name "unconnected-(STMK-PD6-Pad87)") (class "Default")
      (node (ref "STM") (pin "87") (pinfunction "PD6_87") (pintype "bidirectional"))
    )
    (net (code "112") (name "unconnected-(STMM-PE2-Pad1)") (class "Default")
      (node (ref "STM") (pin "1") (pinfunction "PE2_1") (pintype "bidirectional"))
    )
    (net (code "113") (name "unconnected-(STMM-PE3-Pad2)") (class "Default")
      (node (ref "STM") (pin "2") (pinfunction "PE3_2") (pintype "bidirectional"))
    )
    (net (code "114") (name "unconnected-(STMM-PE4-Pad3)") (class "Default")
      (node (ref "STM") (pin "3") (pinfunction "PE4_3") (pintype "bidirectional"))
    )
    (net (code "115") (name "unconnected-(STMM-PE5-Pad4)") (class "Default")
      (node (ref "STM") (pin "4") (pinfunction "PE5_4") (pintype "bidirectional"))
    )
    (net (code "116") (name "unconnected-(STMM-PE6-Pad5)") (class "Default")
      (node (ref "STM") (pin "5") (pinfunction "PE6_5") (pintype "bidirectional"))
    )
    (net (code "117") (name "unconnected-(U$3-3V3-Pad33)") (class "Default")
      (node (ref "U$3") (pin "33") (pinfunction "3V3_33") (pintype "bidirectional"))
    )
    (net (code "118") (name "unconnected-(U$3-NC-Pad24)") (class "Default")
      (node (ref "U$3") (pin "24") (pinfunction "NC_24") (pintype "bidirectional"))
    )
    (net (code "119") (name "unconnected-(U1-AIO0-Pad9)") (class "Default")
      (node (ref "U1") (pin "9") (pinfunction "AIO0_9") (pintype "bidirectional"))
    )
    (net (code "120") (name "unconnected-(U1-AIO1-Pad10)") (class "Default")
      (node (ref "U1") (pin "10") (pinfunction "AIO1_10") (pintype "bidirectional"))
    )
    (net (code "121") (name "unconnected-(U1-CLK-Pad19)") (class "Default")
      (node (ref "U1") (pin "19") (pinfunction "CLK_19") (pintype "bidirectional"))
    )
    (net (code "122") (name "unconnected-(U1-CSB-Pad16)") (class "Default")
      (node (ref "U1") (pin "16") (pinfunction "CSB_16") (pintype "bidirectional"))
    )
    (net (code "123") (name "unconnected-(U1-CTS-Pad3)") (class "Default")
      (node (ref "U1") (pin "3") (pinfunction "CTS_3") (pintype "bidirectional"))
    )
    (net (code "124") (name "unconnected-(U1-GND1-Pad21)") (class "Default")
      (node (ref "U1") (pin "21") (pinfunction "GND1_21") (pintype "bidirectional"))
    )
    (net (code "125") (name "unconnected-(U1-MISO-Pad18)") (class "Default")
      (node (ref "U1") (pin "18") (pinfunction "MISO_18") (pintype "bidirectional"))
    )
    (net (code "126") (name "unconnected-(U1-MOSI-Pad17)") (class "Default")
      (node (ref "U1") (pin "17") (pinfunction "MOSI_17") (pintype "bidirectional"))
    )
    (net (code "127") (name "unconnected-(U1-NC-Pad14)") (class "Default")
      (node (ref "U1") (pin "14") (pinfunction "NC_14") (pintype "bidirectional"))
    )
    (net (code "128") (name "unconnected-(U1-PCM_CLK-Pad5)") (class "Default")
      (node (ref "U1") (pin "5") (pinfunction "PCM_CLK_5") (pintype "bidirectional"))
    )
    (net (code "129") (name "unconnected-(U1-PCM_IN-Pad7)") (class "Default")
      (node (ref "U1") (pin "7") (pinfunction "PCM_IN_7") (pintype "bidirectional"))
    )
    (net (code "130") (name "unconnected-(U1-PCM_OUT-Pad6)") (class "Default")
      (node (ref "U1") (pin "6") (pinfunction "PCM_OUT_6") (pintype "bidirectional"))
    )
    (net (code "131") (name "unconnected-(U1-PCN_SYNC-Pad8)") (class "Default")
      (node (ref "U1") (pin "8") (pinfunction "PCN_SYNC_8") (pintype "bidirectional"))
    )
    (net (code "132") (name "unconnected-(U1-PIO0-Pad23)") (class "Default")
      (node (ref "U1") (pin "23") (pinfunction "PIO0_23") (pintype "bidirectional"))
    )
    (net (code "133") (name "unconnected-(U1-PIO2-Pad25)") (class "Default")
      (node (ref "U1") (pin "25") (pinfunction "PIO2_25") (pintype "bidirectional"))
    )
    (net (code "134") (name "unconnected-(U1-PIO3-Pad26)") (class "Default")
      (node (ref "U1") (pin "26") (pinfunction "PIO3_26") (pintype "bidirectional"))
    )
    (net (code "135") (name "unconnected-(U1-PIO4-Pad27)") (class "Default")
      (node (ref "U1") (pin "27") (pinfunction "PIO4_27") (pintype "bidirectional"))
    )
    (net (code "136") (name "unconnected-(U1-PIO5-Pad28)") (class "Default")
      (node (ref "U1") (pin "28") (pinfunction "PIO5_28") (pintype "bidirectional"))
    )
    (net (code "137") (name "unconnected-(U1-PIO6-Pad29)") (class "Default")
      (node (ref "U1") (pin "29") (pinfunction "PIO6_29") (pintype "bidirectional"))
    )
    (net (code "138") (name "unconnected-(U1-PIO7-Pad30)") (class "Default")
      (node (ref "U1") (pin "30") (pinfunction "PIO7_30") (pintype "bidirectional"))
    )
    (net (code "139") (name "unconnected-(U1-PIO8-Pad31)") (class "Default")
      (node (ref "U1") (pin "31") (pinfunction "PIO8_31") (pintype "bidirectional"))
    )
    (net (code "140") (name "unconnected-(U1-PIO9-Pad32)") (class "Default")
      (node (ref "U1") (pin "32") (pinfunction "PIO9_32") (pintype "bidirectional"))
    )
    (net (code "141") (name "unconnected-(U1-PIO10-Pad33)") (class "Default")
      (node (ref "U1") (pin "33") (pinfunction "PIO10_33") (pintype "bidirectional"))
    )
    (net (code "142") (name "unconnected-(U1-RST-Pad11)") (class "Default")
      (node (ref "U1") (pin "11") (pinfunction "RST_11") (pintype "bidirectional"))
    )
    (net (code "143") (name "unconnected-(U1-RTS-Pad4)") (class "Default")
      (node (ref "U1") (pin "4") (pinfunction "RTS_4") (pintype "bidirectional"))
    )
    (net (code "144") (name "unconnected-(U1-VBUSD+-Pad20)") (class "Default")
      (node (ref "U1") (pin "20") (pinfunction "VBUSD+_20") (pintype "bidirectional"))
    )
    (net (code "145") (name "unconnected-(U1-VBUSD--Pad15)") (class "Default")
      (node (ref "U1") (pin "15") (pinfunction "VBUSD-_15") (pintype "bidirectional"))
    )
  )
)
